# Sheet1.net
KiCad netlist of a schematic drawn in Altium Designer
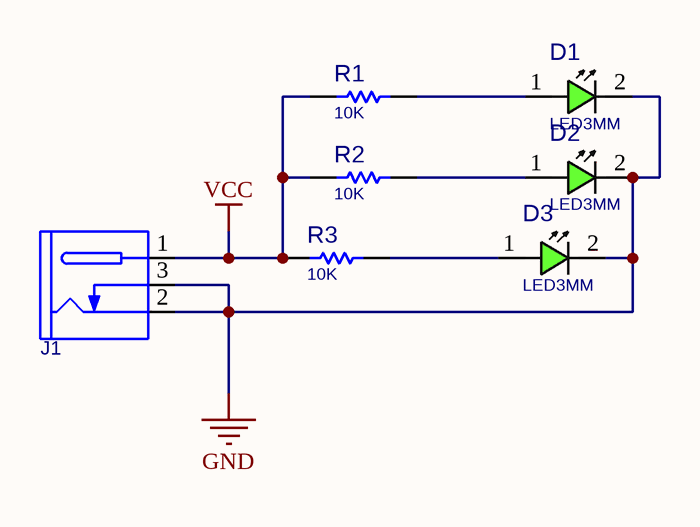
[diagram p0: Sheet1.SchDoc]

(export (version "E")
  (design (tool "Eeschema 10.0.6"))
  (components
    (comp (ref "D1")
      (value "LED3MM")
      (footprint "LED3MM")
      (description "LED, THD, 3MM, GREEN")
      (fields (field (name "MANF") "MANF") (field (name "MANF_P#") "MANF_PART#"))
      (libsource (lib "led(diode)") (part "LED_THD_3MM"))
    )
    (comp (ref "D2")
      (value "LED3MM")
      (footprint "LED3MM")
      (description "LED, THD, 3MM, GREEN")
      (fields (field (name "MANF") "MANF") (field (name "MANF_P#") "MANF_PART#"))
      (libsource (lib "led(diode)") (part "LED_THD_3MM"))
    )
    (comp (ref "D3")
      (value "LED3MM")
      (footprint "LED3MM")
      (description "LED, THD, 3MM, GREEN")
      (fields (field (name "MANF") "MANF") (field (name "MANF_P#") "MANF_PART#"))
      (libsource (lib "led(diode)") (part "LED_THD_3MM"))
    )
    (comp (ref "J1")
      (value "DC_POWER_JACK")
      (footprint "JAC_PWR1")
      (description "CONN, PWR JACK DC, PLUG DIAM 1.0MM RA THD")
      (fields (field (name "MANF") "CUI STACK") (field (name "MANF_P#") "PJ-031CH, PJ-031C"))
      (libsource (lib "conn_powerJack") (part "CONN_PWR_JACKR1"))
    )
    (comp (ref "R1")
      (value "10K")
      (footprint "R025W_AX04")
      (description "RESISTOR, THD")
      (fields (field (name "MANF_P#") "RK73H1ETTP4701F") (field (name "MANF") "KOA SPEER"))
      (libsource (lib "passive_thd") (part "RES_THD"))
    )
    (comp (ref "R2")
      (value "10K")
      (footprint "R025W_AX04")
      (description "RESISTOR, THD")
      (fields (field (name "MANF_P#") "RK73H1ETTP4701F") (field (name "MANF") "KOA SPEER"))
      (libsource (lib "passive_thd") (part "RES_THD"))
    )
    (comp (ref "R3")
      (value "10K")
      (footprint "R025W_AX04")
      (description "RESISTOR, THD")
      (fields (field (name "MANF_P#") "RK73H1ETTP4701F") (field (name "MANF") "KOA SPEER"))
      (libsource (lib "passive_thd") (part "RES_THD"))
    )
  )
  (nets
    (net (code "1") (name "GND") (class "Default")
      (node (ref "D1") (pin "2") (pinfunction "CATHODE_2") (pintype "passive"))
      (node (ref "D2") (pin "2") (pinfunction "CATHODE_2") (pintype "passive"))
      (node (ref "D3") (pin "2") (pinfunction "CATHODE_2") (pintype "passive"))
      (node (ref "J1") (pin "2") (pinfunction "SLEEVE_2") (pintype "power_in"))
      (node (ref "J1") (pin "3") (pinfunction "INSERTION_DET_3") (pintype "power_in"))
    )
    (net (code "2") (name "Net-(D1-ANODE)") (class "Default")
      (node (ref "D1") (pin "1") (pinfunction "ANODE_1") (pintype "passive"))
      (node (ref "R1") (pin "2") (pinfunction "2_2") (pintype "passive"))
    )
    (net (code "3") (name "Net-(D2-ANODE)") (class "Default")
      (node (ref "D2") (pin "1") (pinfunction "ANODE_1") (pintype "passive"))
      (node (ref "R2") (pin "2") (pinfunction "2_2") (pintype "passive"))
    )
    (net (code "4") (name "Net-(D3-ANODE)") (class "Default")
      (node (ref "D3") (pin "1") (pinfunction "ANODE_1") (pintype "passive"))
      (node (ref "R3") (pin "2") (pinfunction "2_2") (pintype "passive"))
    )
    (net (code "5") (name "VCC") (class "Default")
      (node (ref "J1") (pin "1") (pinfunction "TIP_1") (pintype "power_in"))
      (node (ref "R1") (pin "1") (pinfunction "1_1") (pintype "passive"))
      (node (ref "R2") (pin "1") (pinfunction "1_1") (pintype "passive"))
      (node (ref "R3") (pin "1") (pinfunction "1_1") (pintype "passive"))
    )
  )
)
